# 7segement2digits1badidea-mk-4_0.net
KiCad netlist of a schematic drawn in EAGLE
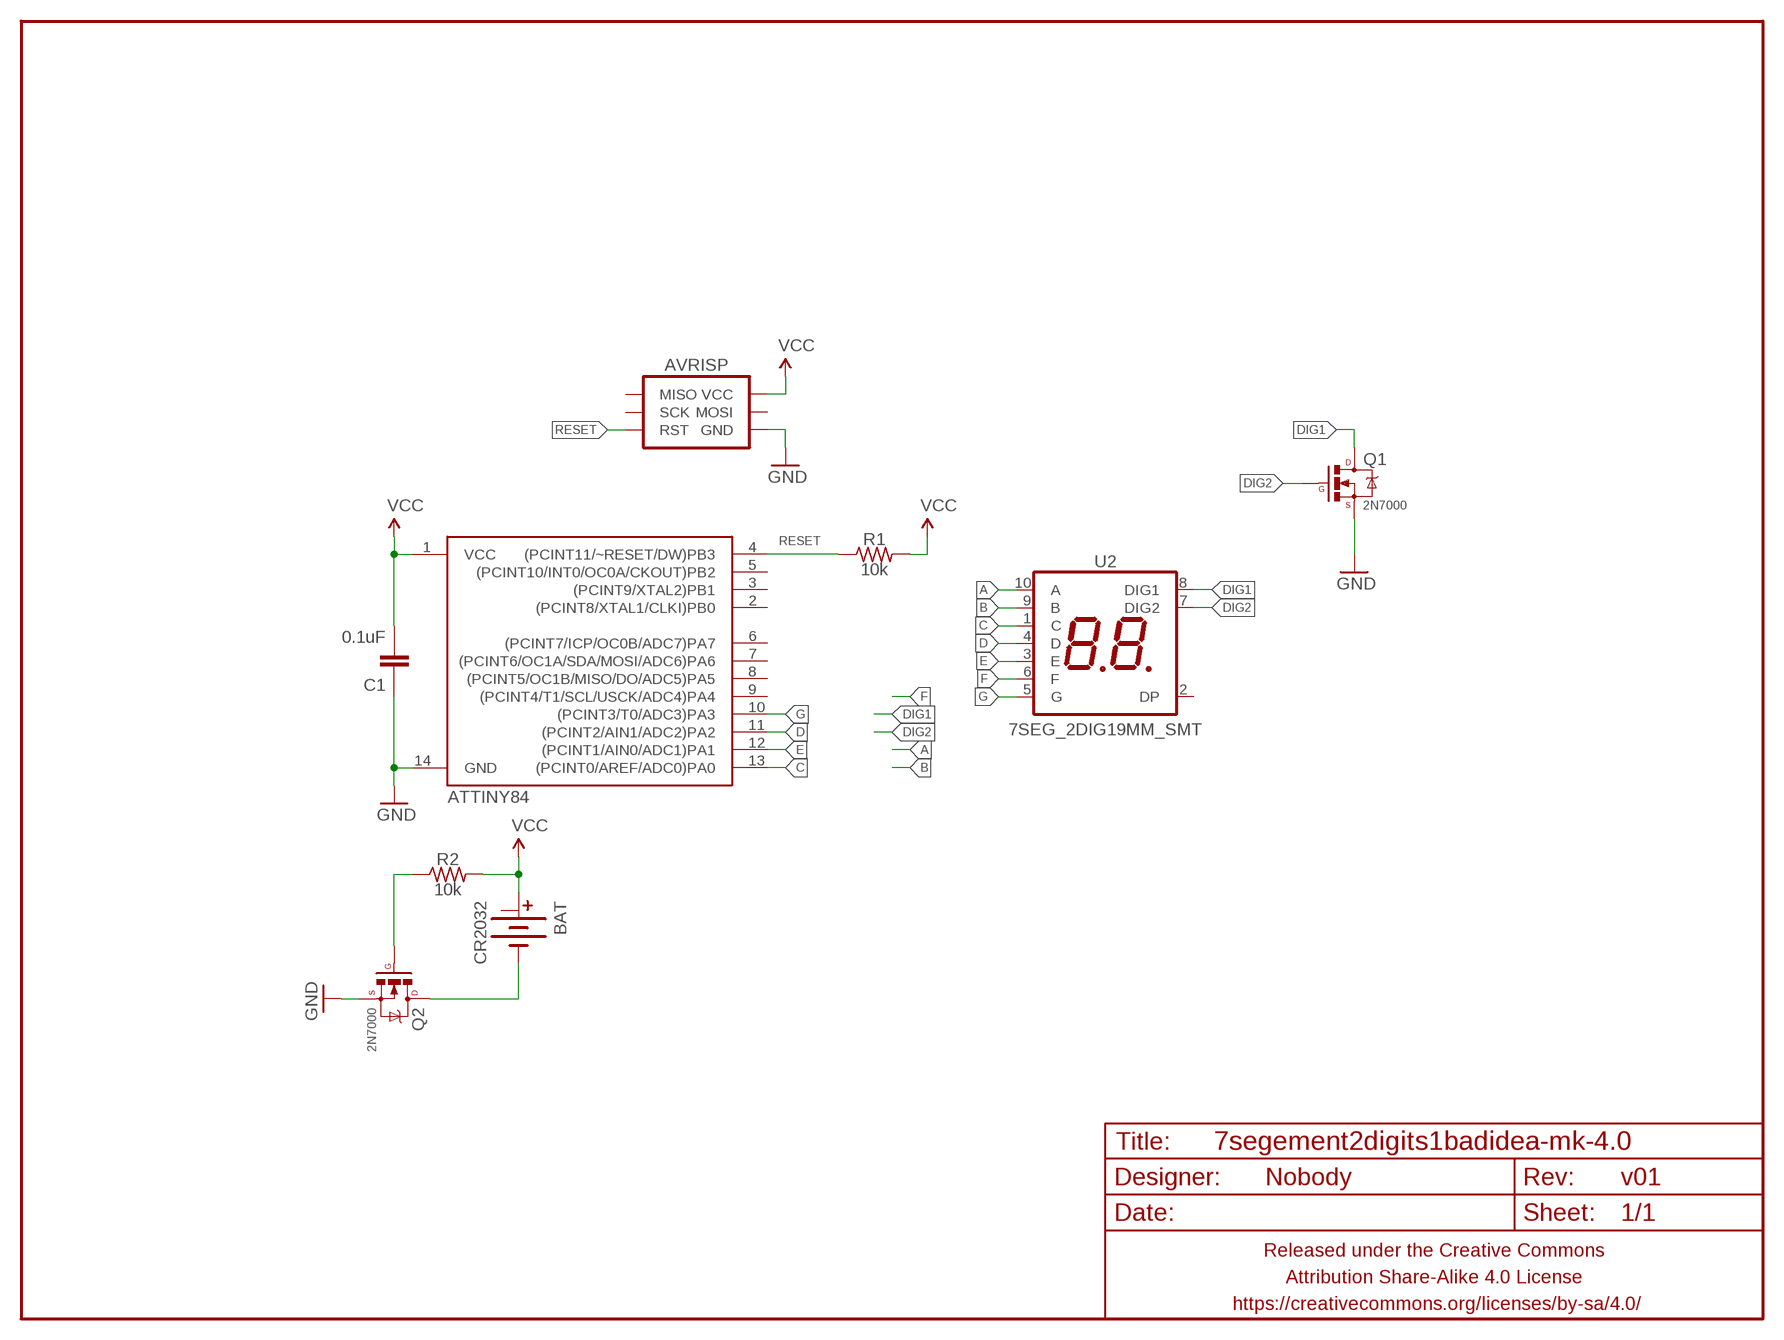
[diagram p0: schematic, sheet 1]

(export (version "E")
  (design (tool "Eeschema 10.0.6"))
  (components
    (comp (ref "AVRISP")
      (value "AVR_SPI_PRG_6PTH")
      (footprint "eagle-import:2X3")
      (libsource (lib "eagle-import") (part "AVR_SPI_PRG_6PTH"))
    )
    (comp (ref "BAT")
      (value "CR2032")
      (footprint "eagle-import:BATTCON_20MM_MINE_STAHPIT")
      (libsource (lib "eagle-import") (part "BATTERY-COINCR2032_SMD_TIGHT"))
    )
    (comp (ref "C1")
      (value "0.1uF")
      (footprint "eagle-import:C0805")
      (libsource (lib "eagle-import") (part "CAPACITOR-CERAMICC0805"))
    )
    (comp (ref "FRAME1")
      (value "FRAME-LETTERNO_PACKAGE")
      (footprint "eagle-import:DUMMY")
      (fields (field (name "DESIGNER") "Nobody"))
      (libsource (lib "eagle-import") (part "FRAME-LETTERNO_PACKAGE"))
    )
    (comp (ref "Q1")
      (value "2N7000")
      (footprint "eagle-import:SOT23")
      (libsource (lib "eagle-import") (part "MOSFET-NCHANNELBSS123LT1G"))
    )
    (comp (ref "Q2")
      (value "2N7000")
      (footprint "eagle-import:SOT23")
      (libsource (lib "eagle-import") (part "MOSFET-NCHANNELBSS123LT1G"))
    )
    (comp (ref "R1")
      (value "10k")
      (footprint "eagle-import:R0805")
      (libsource (lib "eagle-import") (part "RESISTORR0805"))
    )
    (comp (ref "R2")
      (value "10k")
      (footprint "eagle-import:R0805")
      (libsource (lib "eagle-import") (part "RESISTORR0805"))
    )
    (comp (ref "U1")
      (value "ATTINY84")
      (footprint "eagle-import:SO14")
      (libsource (lib "eagle-import") (part "ATTINY84"))
    )
    (comp (ref "U2")
      (value "7SEG_2DIG19MM_SMT")
      (footprint "eagle-import:7SEG_2DIG_19MM_SMT")
      (libsource (lib "eagle-import") (part "7SEG_2DIG19MM_SMT"))
    )
  )
  (nets
    (net (code "1") (name "A") (class "Default")
      (node (ref "U2") (pin "10") (pinfunction "A_10") (pintype "passive"))
    )
    (net (code "2") (name "B") (class "Default")
      (node (ref "U2") (pin "9") (pinfunction "B_9") (pintype "passive"))
    )
    (net (code "3") (name "C") (class "Default")
      (node (ref "U1") (pin "13") (pinfunction "(PCINT0/AREF/ADC0)PA0_13") (pintype "bidirectional"))
      (node (ref "U2") (pin "1") (pinfunction "C_1") (pintype "passive"))
    )
    (net (code "4") (name "D") (class "Default")
      (node (ref "U1") (pin "11") (pinfunction "(PCINT2/AIN1/ADC2)PA2_11") (pintype "bidirectional"))
      (node (ref "U2") (pin "4") (pinfunction "D_4") (pintype "passive"))
    )
    (net (code "5") (name "DIG1") (class "Default")
      (node (ref "Q1") (pin "3") (pinfunction "D_3") (pintype "passive"))
      (node (ref "U2") (pin "8") (pinfunction "DIG1_8") (pintype "passive"))
    )
    (net (code "6") (name "DIG2") (class "Default")
      (node (ref "Q1") (pin "1") (pinfunction "G_1") (pintype "passive"))
      (node (ref "U2") (pin "7") (pinfunction "DIG2_7") (pintype "passive"))
    )
    (net (code "7") (name "E") (class "Default")
      (node (ref "U1") (pin "12") (pinfunction "(PCINT1/AIN0/ADC1)PA1_12") (pintype "bidirectional"))
      (node (ref "U2") (pin "3") (pinfunction "E_3") (pintype "passive"))
    )
    (net (code "8") (name "F") (class "Default")
      (node (ref "U2") (pin "6") (pinfunction "F_6") (pintype "passive"))
    )
    (net (code "9") (name "G") (class "Default")
      (node (ref "U1") (pin "10") (pinfunction "(PCINT3/T0/ADC3)PA3_10") (pintype "bidirectional"))
      (node (ref "U2") (pin "5") (pinfunction "G_5") (pintype "passive"))
    )
    (net (code "10") (name "GND") (class "Default")
      (node (ref "AVRISP") (pin "6") (pinfunction "GND_6") (pintype "passive"))
      (node (ref "C1") (pin "1") (pinfunction "1_1") (pintype "passive"))
      (node (ref "Q1") (pin "2") (pinfunction "S_2") (pintype "passive"))
      (node (ref "Q2") (pin "2") (pinfunction "S_2") (pintype "passive"))
      (node (ref "U1") (pin "14") (pinfunction "GND_14") (pintype "bidirectional"))
    )
    (net (code "11") (name "Net-(BAT--)") (class "Default")
      (node (ref "BAT") (pin "BOTTOM") (pinfunction "-_BOTTOM") (pintype "bidirectional"))
      (node (ref "Q2") (pin "3") (pinfunction "D_3") (pintype "passive"))
    )
    (net (code "12") (name "Net-(Q2-G)") (class "Default")
      (node (ref "Q2") (pin "1") (pinfunction "G_1") (pintype "passive"))
      (node (ref "R2") (pin "1") (pinfunction "1_1") (pintype "passive"))
    )
    (net (code "13") (name "RESET") (class "Default")
      (node (ref "AVRISP") (pin "5") (pinfunction "RST_5") (pintype "passive"))
      (node (ref "R1") (pin "1") (pinfunction "1_1") (pintype "passive"))
      (node (ref "U1") (pin "4") (pinfunction "(PCINT11/~{RESET/DW})PB3_4") (pintype "bidirectional"))
    )
    (net (code "14") (name "VCC") (class "Default")
      (node (ref "AVRISP") (pin "2") (pinfunction "VCC_2") (pintype "passive"))
      (node (ref "BAT") (pin "TOP@1") (pinfunction "+_TOP@1") (pintype "bidirectional"))
      (node (ref "C1") (pin "2") (pinfunction "2_2") (pintype "passive"))
      (node (ref "R1") (pin "2") (pinfunction "2_2") (pintype "passive"))
      (node (ref "R2") (pin "2") (pinfunction "2_2") (pintype "passive"))
      (node (ref "U1") (pin "1") (pinfunction "VCC_1") (pintype "bidirectional"))
    )
    (net (code "15") (name "unconnected-(AVRISP-MISO-Pad1)") (class "Default")
      (node (ref "AVRISP") (pin "1") (pinfunction "MISO_1") (pintype "passive"))
    )
    (net (code "16") (name "unconnected-(AVRISP-MOSI-Pad4)") (class "Default")
      (node (ref "AVRISP") (pin "4") (pinfunction "MOSI_4") (pintype "passive"))
    )
    (net (code "17") (name "unconnected-(AVRISP-SCK-Pad3)") (class "Default")
      (node (ref "AVRISP") (pin "3") (pinfunction "SCK_3") (pintype "passive"))
    )
    (net (code "18") (name "unconnected-(BAT-+1-PadTOP@2)") (class "Default")
      (node (ref "BAT") (pin "TOP@2") (pinfunction "+1_TOP@2") (pintype "bidirectional"))
    )
    (net (code "19") (name "unconnected-(U1-(PCINT4{slash}T1{slash}SCL{slash}USCK{slash}ADC4)PA4-Pad9)") (class "Default")
      (node (ref "U1") (pin "9") (pinfunction "(PCINT4/T1/SCL/USCK/ADC4)PA4_9") (pintype "bidirectional"))
    )
    (net (code "20") (name "unconnected-(U1-(PCINT5{slash}OC1B{slash}MISO{slash}DO{slash}ADC5)PA5-Pad8)") (class "Default")
      (node (ref "U1") (pin "8") (pinfunction "(PCINT5/OC1B/MISO/DO/ADC5)PA5_8") (pintype "bidirectional"))
    )
    (net (code "21") (name "unconnected-(U1-(PCINT6{slash}OC1A{slash}SDA{slash}MOSI{slash}ADC6)PA6-Pad7)") (class "Default")
      (node (ref "U1") (pin "7") (pinfunction "(PCINT6/OC1A/SDA/MOSI/ADC6)PA6_7") (pintype "bidirectional"))
    )
    (net (code "22") (name "unconnected-(U1-(PCINT7{slash}ICP{slash}OC0B{slash}ADC7)PA7-Pad6)") (class "Default")
      (node (ref "U1") (pin "6") (pinfunction "(PCINT7/ICP/OC0B/ADC7)PA7_6") (pintype "bidirectional"))
    )
    (net (code "23") (name "unconnected-(U1-(PCINT8{slash}XTAL1{slash}CLKI)PB0-Pad2)") (class "Default")
      (node (ref "U1") (pin "2") (pinfunction "(PCINT8/XTAL1/CLKI)PB0_2") (pintype "bidirectional"))
    )
    (net (code "24") (name "unconnected-(U1-(PCINT9{slash}XTAL2)PB1-Pad3)") (class "Default")
      (node (ref "U1") (pin "3") (pinfunction "(PCINT9/XTAL2)PB1_3") (pintype "bidirectional"))
    )
    (net (code "25") (name "unconnected-(U1-(PCINT10{slash}INT0{slash}OC0A{slash}CKOUT)PB2-Pad5)") (class "Default")
      (node (ref "U1") (pin "5") (pinfunction "(PCINT10/INT0/OC0A/CKOUT)PB2_5") (pintype "bidirectional"))
    )
    (net (code "26") (name "unconnected-(U2-DP-Pad2)") (class "Default")
      (node (ref "U2") (pin "2") (pinfunction "DP_2") (pintype "passive"))
    )
  )
)
